# data_bluetooth.net
KiCad netlist of a schematic drawn in Altium Designer
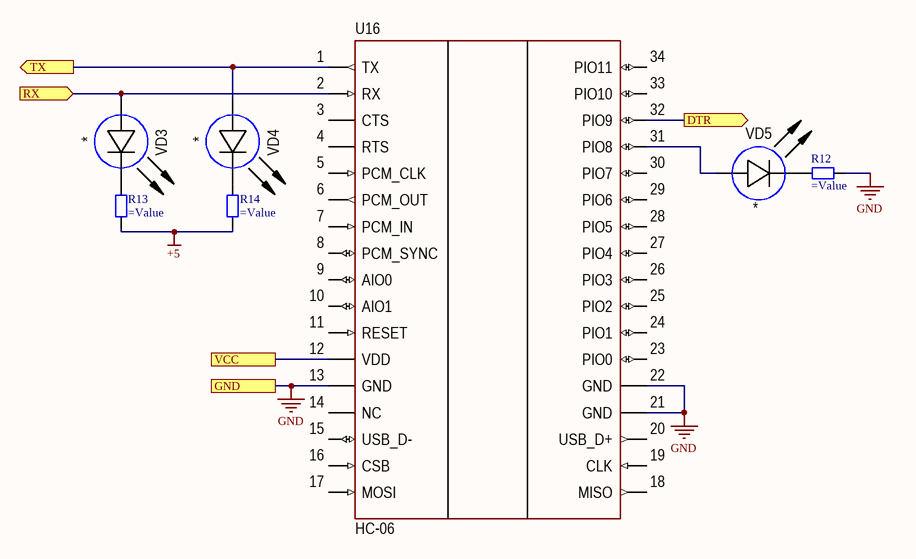
[diagram p0: data bluetooth.SchDoc]

(export (version "E")
  (design (tool "Eeschema 10.0.6"))
  (components
    (comp (ref "R12")
      (value "~")
      (footprint "res0603")
      (libsource (lib "AlexChistiakov") (part "Resistor SMD"))
    )
    (comp (ref "R13")
      (value "~")
      (footprint "res0603")
      (libsource (lib "AlexChistiakov") (part "Resistor SMD"))
    )
    (comp (ref "R14")
      (value "~")
      (footprint "res0603")
      (libsource (lib "AlexChistiakov") (part "Resistor SMD"))
    )
    (comp (ref "U16")
      (value "HC-06")
      (footprint "custom:MOD: HC-05")
      (description "Bluetooth")
      (fields (field (name "MANUFACTURER") "China"))
      (libsource (lib "Module") (part "HC-06"))
    )
    (comp (ref "VD3") (value "*") (footprint "CH0603LB") (libsource (lib "Discrete") (part "LED")))
    (comp (ref "VD4") (value "*") (footprint "CH0603LB") (libsource (lib "Discrete") (part "LED")))
    (comp (ref "VD5") (value "*") (footprint "CH0603LB") (libsource (lib "Discrete") (part "LED")))
  )
  (nets
    (net (code "1") (name "+5") (class "Default")
      (node (ref "R13") (pin "1") (pinfunction "1_1") (pintype "passive"))
      (node (ref "R14") (pin "1") (pinfunction "1_1") (pintype "passive"))
    )
    (net (code "2") (name "/DTR") (class "Default")
      (node (ref "U16") (pin "32") (pinfunction "PIO9_32") (pintype "bidirectional"))
    )
    (net (code "3") (name "/RX") (class "Default")
      (node (ref "U16") (pin "2") (pinfunction "RX_2") (pintype "input"))
      (node (ref "VD3") (pin "1") (pinfunction "A_1") (pintype "passive"))
    )
    (net (code "4") (name "/TX") (class "Default")
      (node (ref "U16") (pin "1") (pinfunction "TX_1") (pintype "output"))
      (node (ref "VD4") (pin "1") (pinfunction "A_1") (pintype "passive"))
    )
    (net (code "5") (name "/VCC") (class "Default")
      (node (ref "U16") (pin "12") (pinfunction "VDD_12") (pintype "passive"))
    )
    (net (code "6") (name "GND") (class "Default")
      (node (ref "R12") (pin "1") (pinfunction "1_1") (pintype "passive"))
      (node (ref "U16") (pin "13") (pinfunction "GND_13") (pintype "passive"))
      (node (ref "U16") (pin "21") (pinfunction "GND_21") (pintype "passive"))
      (node (ref "U16") (pin "22") (pinfunction "GND_22") (pintype "passive"))
    )
    (net (code "7") (name "Net-(U16-PIO8)") (class "Default")
      (node (ref "U16") (pin "31") (pinfunction "PIO8_31") (pintype "bidirectional"))
      (node (ref "VD5") (pin "1") (pinfunction "A_1") (pintype "passive"))
    )
    (net (code "8") (name "Net-(VD3-C)") (class "Default")
      (node (ref "R13") (pin "2") (pinfunction "2_2") (pintype "passive"))
      (node (ref "VD3") (pin "2") (pinfunction "C_2") (pintype "passive"))
    )
    (net (code "9") (name "Net-(VD4-C)") (class "Default")
      (node (ref "R14") (pin "2") (pinfunction "2_2") (pintype "passive"))
      (node (ref "VD4") (pin "2") (pinfunction "C_2") (pintype "passive"))
    )
    (net (code "10") (name "Net-(VD5-C)") (class "Default")
      (node (ref "R12") (pin "2") (pinfunction "2_2") (pintype "passive"))
      (node (ref "VD5") (pin "2") (pinfunction "C_2") (pintype "passive"))
    )
    (net (code "11") (name "unconnected-(U16-AIO0-Pad9)") (class "Default")
      (node (ref "U16") (pin "9") (pinfunction "AIO0_9") (pintype "bidirectional"))
    )
    (net (code "12") (name "unconnected-(U16-AIO1-Pad10)") (class "Default")
      (node (ref "U16") (pin "10") (pinfunction "AIO1_10") (pintype "bidirectional"))
    )
    (net (code "13") (name "unconnected-(U16-CLK-Pad19)") (class "Default")
      (node (ref "U16") (pin "19") (pinfunction "CLK_19") (pintype "input"))
    )
    (net (code "14") (name "unconnected-(U16-CSB-Pad16)") (class "Default")
      (node (ref "U16") (pin "16") (pinfunction "CSB_16") (pintype "input"))
    )
    (net (code "15") (name "unconnected-(U16-CTS-Pad3)") (class "Default")
      (node (ref "U16") (pin "3") (pinfunction "CTS_3") (pintype "passive"))
    )
    (net (code "16") (name "unconnected-(U16-MISO-Pad18)") (class "Default")
      (node (ref "U16") (pin "18") (pinfunction "MISO_18") (pintype "output"))
    )
    (net (code "17") (name "unconnected-(U16-MOSI-Pad17)") (class "Default")
      (node (ref "U16") (pin "17") (pinfunction "MOSI_17") (pintype "input"))
    )
    (net (code "18") (name "unconnected-(U16-NC-Pad14)") (class "Default")
      (node (ref "U16") (pin "14") (pinfunction "NC_14") (pintype "passive"))
    )
    (net (code "19") (name "unconnected-(U16-PCM_CLK-Pad5)") (class "Default")
      (node (ref "U16") (pin "5") (pinfunction "PCM_CLK_5") (pintype "input"))
    )
    (net (code "20") (name "unconnected-(U16-PCM_IN-Pad7)") (class "Default")
      (node (ref "U16") (pin "7") (pinfunction "PCM_IN_7") (pintype "input"))
    )
    (net (code "21") (name "unconnected-(U16-PCM_OUT-Pad6)") (class "Default")
      (node (ref "U16") (pin "6") (pinfunction "PCM_OUT_6") (pintype "output"))
    )
    (net (code "22") (name "unconnected-(U16-PCM_SYNC-Pad8)") (class "Default")
      (node (ref "U16") (pin "8") (pinfunction "PCM_SYNC_8") (pintype "bidirectional"))
    )
    (net (code "23") (name "unconnected-(U16-PIO0-Pad23)") (class "Default")
      (node (ref "U16") (pin "23") (pinfunction "PIO0_23") (pintype "bidirectional"))
    )
    (net (code "24") (name "unconnected-(U16-PIO1-Pad24)") (class "Default")
      (node (ref "U16") (pin "24") (pinfunction "PIO1_24") (pintype "bidirectional"))
    )
    (net (code "25") (name "unconnected-(U16-PIO2-Pad25)") (class "Default")
      (node (ref "U16") (pin "25") (pinfunction "PIO2_25") (pintype "bidirectional"))
    )
    (net (code "26") (name "unconnected-(U16-PIO3-Pad26)") (class "Default")
      (node (ref "U16") (pin "26") (pinfunction "PIO3_26") (pintype "bidirectional"))
    )
    (net (code "27") (name "unconnected-(U16-PIO4-Pad27)") (class "Default")
      (node (ref "U16") (pin "27") (pinfunction "PIO4_27") (pintype "bidirectional"))
    )
    (net (code "28") (name "unconnected-(U16-PIO5-Pad28)") (class "Default")
      (node (ref "U16") (pin "28") (pinfunction "PIO5_28") (pintype "bidirectional"))
    )
    (net (code "29") (name "unconnected-(U16-PIO6-Pad29)") (class "Default")
      (node (ref "U16") (pin "29") (pinfunction "PIO6_29") (pintype "bidirectional"))
    )
    (net (code "30") (name "unconnected-(U16-PIO7-Pad30)") (class "Default")
      (node (ref "U16") (pin "30") (pinfunction "PIO7_30") (pintype "bidirectional"))
    )
    (net (code "31") (name "unconnected-(U16-PIO10-Pad33)") (class "Default")
      (node (ref "U16") (pin "33") (pinfunction "PIO10_33") (pintype "bidirectional"))
    )
    (net (code "32") (name "unconnected-(U16-PIO11-Pad34)") (class "Default")
      (node (ref "U16") (pin "34") (pinfunction "PIO11_34") (pintype "bidirectional"))
    )
    (net (code "33") (name "unconnected-(U16-RESET-Pad11)") (class "Default")
      (node (ref "U16") (pin "11") (pinfunction "RESET_11") (pintype "input"))
    )
    (net (code "34") (name "unconnected-(U16-RTS-Pad4)") (class "Default")
      (node (ref "U16") (pin "4") (pinfunction "RTS_4") (pintype "passive"))
    )
    (net (code "35") (name "unconnected-(U16-USB_D+-Pad20)") (class "Default")
      (node (ref "U16") (pin "20") (pinfunction "USB_D+_20") (pintype "output"))
    )
    (net (code "36") (name "unconnected-(U16-USB_D--Pad15)") (class "Default")
      (node (ref "U16") (pin "15") (pinfunction "USB_D-_15") (pintype "bidirectional"))
    )
  )
)
